# Connectors.net
KiCad netlist of a schematic drawn in Altium Designer
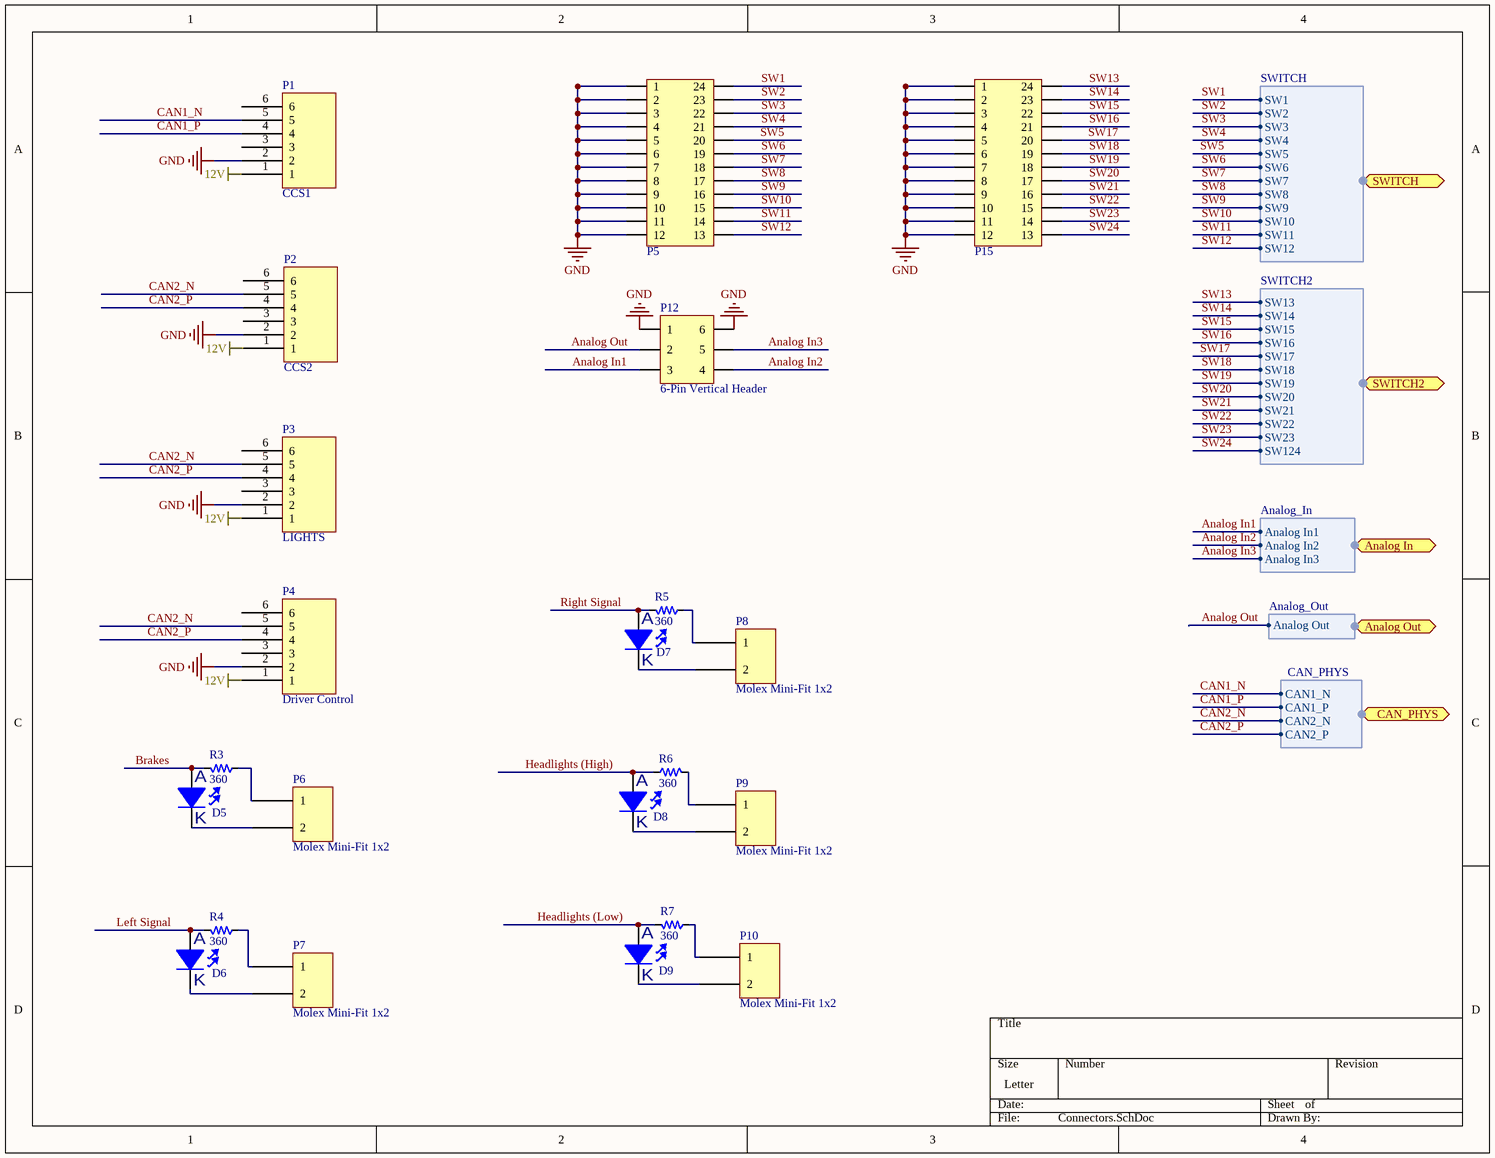
[diagram p0: Connectors.SchDoc]

(export (version "E")
  (design (tool "Eeschema 10.0.6"))
  (components
    (comp (ref "D5")
      (value "LED RED")
      (footprint "RED LED")
      (libsource (lib "LED RED 150141RS73100") (part "LED RED"))
    )
    (comp (ref "D6")
      (value "LED RED")
      (footprint "RED LED")
      (libsource (lib "LED RED 150141RS73100") (part "LED RED"))
    )
    (comp (ref "D7")
      (value "LED RED")
      (footprint "RED LED")
      (libsource (lib "LED RED 150141RS73100") (part "LED RED"))
    )
    (comp (ref "D8")
      (value "LED RED")
      (footprint "RED LED")
      (libsource (lib "LED RED 150141RS73100") (part "LED RED"))
    )
    (comp (ref "D9")
      (value "LED RED")
      (footprint "RED LED")
      (libsource (lib "LED RED 150141RS73100") (part "LED RED"))
    )
    (comp (ref "P1")
      (value "CCS1")
      (footprint "PCB_MLX_MICROFIT_3X2")
      (libsource (lib "SCH_MLX_MICROFIT_3X2_P") (part "SCH_MLX_MICROFIT_3X2"))
    )
    (comp (ref "P2")
      (value "CCS2")
      (footprint "PCB_MLX_MICROFIT_3X2")
      (libsource (lib "SCH_MLX_MICROFIT_3X2_P") (part "SCH_MLX_MICROFIT_3X2"))
    )
    (comp (ref "P3")
      (value "LIGHTS")
      (footprint "PCB_MLX_MICROFIT_3X2")
      (libsource (lib "SCH_MLX_MICROFIT_3X2_P") (part "SCH_MLX_MICROFIT_3X2"))
    )
    (comp (ref "P4")
      (value "Driver Control")
      (footprint "PCB_MLX_MICROFIT_3X2")
      (libsource (lib "SCH_MLX_MICROFIT_3X2_P") (part "SCH_MLX_MICROFIT_3X2"))
    )
    (comp (ref "P5")
      (value "24-Pin Vertical Header")
      (footprint "24-Pin Vertical Header")
      (fields (field (name "MANUFACTURER") "Sullins"))
      (libsource (lib "24 Pin 100 mil Vertical Header - Through Hole") (part "24-Pin Vertical Header"))
    )
    (comp (ref "P6")
      (value "Molex Mini-Fit 1x2")
      (footprint "Molex Mini-Fit Jr 2x1")
      (libsource (lib "Molex Mini-Fit Jr 1x2") (part "Molex Mini-Fit 1x2"))
    )
    (comp (ref "P7")
      (value "Molex Mini-Fit 1x2")
      (footprint "Molex Mini-Fit Jr 2x1")
      (libsource (lib "Molex Mini-Fit Jr 1x2") (part "Molex Mini-Fit 1x2"))
    )
    (comp (ref "P8")
      (value "Molex Mini-Fit 1x2")
      (footprint "Molex Mini-Fit Jr 2x1")
      (libsource (lib "Molex Mini-Fit Jr 1x2") (part "Molex Mini-Fit 1x2"))
    )
    (comp (ref "P9")
      (value "Molex Mini-Fit 1x2")
      (footprint "Molex Mini-Fit Jr 2x1")
      (libsource (lib "Molex Mini-Fit Jr 1x2") (part "Molex Mini-Fit 1x2"))
    )
    (comp (ref "P10")
      (value "Molex Mini-Fit 1x2")
      (footprint "Molex Mini-Fit Jr 2x1")
      (libsource (lib "Molex Mini-Fit Jr 1x2") (part "Molex Mini-Fit 1x2"))
    )
    (comp (ref "P12")
      (value "6-Pin Vertical Header")
      (footprint "6-Pin Vertical Header")
      (fields (field (name "MANUFACTURER") "Sullins"))
      (libsource (lib "6 Pin 100 mil Vertical Header - Through Hole") (part "6-Pin Vertical Header"))
    )
    (comp (ref "P15")
      (value "24-Pin Vertical Header")
      (footprint "24-Pin Vertical Header")
      (fields (field (name "MANUFACTURER") "Sullins"))
      (libsource (lib "24 Pin 100 mil Vertical Header - Through Hole") (part "24-Pin Vertical Header"))
    )
    (comp (ref "R3")
      (value "SCH_GENERIC_RESISTOR_0603")
      (footprint "PCB_GENERIC_SMD_0603")
      (description "Generic SMD resistor 0603")
      (fields (field (name "RESISTANCE") "360"))
      (libsource (lib "SCH_GENERIC_RESISTOR_0603") (part "SCH_GENERIC_RESISTOR_0603"))
    )
    (comp (ref "R4")
      (value "SCH_GENERIC_RESISTOR_0603")
      (footprint "PCB_GENERIC_SMD_0603")
      (description "Generic SMD resistor 0603")
      (fields (field (name "RESISTANCE") "360"))
      (libsource (lib "SCH_GENERIC_RESISTOR_0603") (part "SCH_GENERIC_RESISTOR_0603"))
    )
    (comp (ref "R5")
      (value "SCH_GENERIC_RESISTOR_0603")
      (footprint "PCB_GENERIC_SMD_0603")
      (description "Generic SMD resistor 0603")
      (fields (field (name "RESISTANCE") "360"))
      (libsource (lib "SCH_GENERIC_RESISTOR_0603") (part "SCH_GENERIC_RESISTOR_0603"))
    )
    (comp (ref "R6")
      (value "SCH_GENERIC_RESISTOR_0603")
      (footprint "PCB_GENERIC_SMD_0603")
      (description "Generic SMD resistor 0603")
      (fields (field (name "RESISTANCE") "360"))
      (libsource (lib "SCH_GENERIC_RESISTOR_0603") (part "SCH_GENERIC_RESISTOR_0603"))
    )
    (comp (ref "R7")
      (value "SCH_GENERIC_RESISTOR_0603")
      (footprint "PCB_GENERIC_SMD_0603")
      (description "Generic SMD resistor 0603")
      (fields (field (name "RESISTANCE") "360"))
      (libsource (lib "SCH_GENERIC_RESISTOR_0603") (part "SCH_GENERIC_RESISTOR_0603"))
    )
  )
  (nets
    (net (code "6") (name "/Analog In1") (class "Default")
      (node (ref "P12") (pin "3") (pinfunction "3_3") (pintype "passive"))
    )
    (net (code "7") (name "/Analog In2") (class "Default")
      (node (ref "P12") (pin "4") (pinfunction "4_4") (pintype "passive"))
    )
    (net (code "8") (name "/Analog In3") (class "Default")
      (node (ref "P12") (pin "5") (pinfunction "5_5") (pintype "passive"))
    )
    (net (code "9") (name "/Analog Out") (class "Default")
      (node (ref "P12") (pin "2") (pinfunction "2_2") (pintype "passive"))
    )
    (net (code "10") (name "/Brakes") (class "Default")
      (node (ref "D5") (pin "2") (pintype "passive"))
      (node (ref "R3") (pin "2") (pinfunction "2_2") (pintype "passive"))
    )
    (net (code "11") (name "/CAN1_N") (class "Default")
      (node (ref "P1") (pin "5") (pinfunction "5_5") (pintype "passive"))
    )
    (net (code "12") (name "/CAN1_P") (class "Default")
      (node (ref "P1") (pin "4") (pinfunction "4_4") (pintype "passive"))
    )
    (net (code "13") (name "/CAN2_N") (class "Default")
      (node (ref "P2") (pin "5") (pinfunction "5_5") (pintype "passive"))
      (node (ref "P3") (pin "5") (pinfunction "5_5") (pintype "passive"))
      (node (ref "P4") (pin "5") (pinfunction "5_5") (pintype "passive"))
    )
    (net (code "14") (name "/CAN2_P") (class "Default")
      (node (ref "P2") (pin "4") (pinfunction "4_4") (pintype "passive"))
      (node (ref "P3") (pin "4") (pinfunction "4_4") (pintype "passive"))
      (node (ref "P4") (pin "4") (pinfunction "4_4") (pintype "passive"))
    )
    (net (code "15") (name "/Headlights (High)") (class "Default")
      (node (ref "D8") (pin "2") (pintype "passive"))
      (node (ref "R6") (pin "1") (pinfunction "1_1") (pintype "passive"))
    )
    (net (code "16") (name "/Headlights (Low)") (class "Default")
      (node (ref "D9") (pin "2") (pintype "passive"))
      (node (ref "R7") (pin "2") (pinfunction "2_2") (pintype "passive"))
    )
    (net (code "17") (name "/Left Signal") (class "Default")
      (node (ref "D6") (pin "2") (pintype "passive"))
      (node (ref "R4") (pin "2") (pinfunction "2_2") (pintype "passive"))
    )
    (net (code "18") (name "/Right Signal") (class "Default")
      (node (ref "D7") (pin "2") (pintype "passive"))
      (node (ref "R5") (pin "2") (pinfunction "2_2") (pintype "passive"))
    )
    (net (code "19") (name "/SW1") (class "Default")
      (node (ref "P5") (pin "24") (pinfunction "24_24") (pintype "passive"))
    )
    (net (code "20") (name "/SW2") (class "Default")
      (node (ref "P5") (pin "23") (pinfunction "23_23") (pintype "passive"))
    )
    (net (code "21") (name "/SW3") (class "Default")
      (node (ref "P5") (pin "22") (pinfunction "22_22") (pintype "passive"))
    )
    (net (code "22") (name "/SW4") (class "Default")
      (node (ref "P5") (pin "21") (pinfunction "21_21") (pintype "passive"))
    )
    (net (code "23") (name "/SW5") (class "Default")
      (node (ref "P5") (pin "20") (pinfunction "20_20") (pintype "passive"))
    )
    (net (code "24") (name "/SW6") (class "Default")
      (node (ref "P5") (pin "19") (pinfunction "19_19") (pintype "passive"))
    )
    (net (code "25") (name "/SW7") (class "Default")
      (node (ref "P5") (pin "18") (pinfunction "18_18") (pintype "passive"))
    )
    (net (code "26") (name "/SW8") (class "Default")
      (node (ref "P5") (pin "17") (pinfunction "17_17") (pintype "passive"))
    )
    (net (code "27") (name "/SW9") (class "Default")
      (node (ref "P5") (pin "16") (pinfunction "16_16") (pintype "passive"))
    )
    (net (code "28") (name "/SW10") (class "Default")
      (node (ref "P5") (pin "15") (pinfunction "15_15") (pintype "passive"))
    )
    (net (code "29") (name "/SW11") (class "Default")
      (node (ref "P5") (pin "14") (pinfunction "14_14") (pintype "passive"))
    )
    (net (code "30") (name "/SW12") (class "Default")
      (node (ref "P5") (pin "13") (pinfunction "13_13") (pintype "passive"))
    )
    (net (code "31") (name "/SW13") (class "Default")
      (node (ref "P15") (pin "24") (pinfunction "24_24") (pintype "passive"))
    )
    (net (code "32") (name "/SW14") (class "Default")
      (node (ref "P15") (pin "23") (pinfunction "23_23") (pintype "passive"))
    )
    (net (code "33") (name "/SW15") (class "Default")
      (node (ref "P15") (pin "22") (pinfunction "22_22") (pintype "passive"))
    )
    (net (code "34") (name "/SW16") (class "Default")
      (node (ref "P15") (pin "21") (pinfunction "21_21") (pintype "passive"))
    )
    (net (code "35") (name "/SW17") (class "Default")
      (node (ref "P15") (pin "20") (pinfunction "20_20") (pintype "passive"))
    )
    (net (code "36") (name "/SW18") (class "Default")
      (node (ref "P15") (pin "19") (pinfunction "19_19") (pintype "passive"))
    )
    (net (code "37") (name "/SW19") (class "Default")
      (node (ref "P15") (pin "18") (pinfunction "18_18") (pintype "passive"))
    )
    (net (code "38") (name "/SW20") (class "Default")
      (node (ref "P15") (pin "17") (pinfunction "17_17") (pintype "passive"))
    )
    (net (code "39") (name "/SW21") (class "Default")
      (node (ref "P15") (pin "16") (pinfunction "16_16") (pintype "passive"))
    )
    (net (code "40") (name "/SW22") (class "Default")
      (node (ref "P15") (pin "15") (pinfunction "15_15") (pintype "passive"))
    )
    (net (code "41") (name "/SW23") (class "Default")
      (node (ref "P15") (pin "14") (pinfunction "14_14") (pintype "passive"))
    )
    (net (code "42") (name "/SW24") (class "Default")
      (node (ref "P15") (pin "13") (pinfunction "13_13") (pintype "passive"))
    )
    (net (code "48") (name "12V") (class "Default")
      (node (ref "P1") (pin "1") (pinfunction "1_1") (pintype "passive"))
      (node (ref "P2") (pin "1") (pinfunction "1_1") (pintype "passive"))
      (node (ref "P3") (pin "1") (pinfunction "1_1") (pintype "passive"))
      (node (ref "P4") (pin "1") (pinfunction "1_1") (pintype "passive"))
    )
    (net (code "49") (name "GND") (class "Default")
      (node (ref "P1") (pin "2") (pinfunction "2_2") (pintype "passive"))
      (node (ref "P12") (pin "1") (pinfunction "1_1") (pintype "passive"))
      (node (ref "P12") (pin "6") (pinfunction "6_6") (pintype "passive"))
      (node (ref "P15") (pin "1") (pinfunction "1_1") (pintype "passive"))
      (node (ref "P15") (pin "10") (pinfunction "10_10") (pintype "passive"))
      (node (ref "P15") (pin "11") (pinfunction "11_11") (pintype "passive"))
      (node (ref "P15") (pin "12") (pinfunction "12_12") (pintype "passive"))
      (node (ref "P15") (pin "2") (pinfunction "2_2") (pintype "passive"))
      (node (ref "P15") (pin "3") (pinfunction "3_3") (pintype "passive"))
      (node (ref "P15") (pin "4") (pinfunction "4_4") (pintype "passive"))
      (node (ref "P15") (pin "5") (pinfunction "5_5") (pintype "passive"))
      (node (ref "P15") (pin "6") (pinfunction "6_6") (pintype "passive"))
      (node (ref "P15") (pin "7") (pinfunction "7_7") (pintype "passive"))
      (node (ref "P15") (pin "8") (pinfunction "8_8") (pintype "passive"))
      (node (ref "P15") (pin "9") (pinfunction "9_9") (pintype "passive"))
      (node (ref "P2") (pin "2") (pinfunction "2_2") (pintype "passive"))
      (node (ref "P3") (pin "2") (pinfunction "2_2") (pintype "passive"))
      (node (ref "P4") (pin "2") (pinfunction "2_2") (pintype "passive"))
      (node (ref "P5") (pin "1") (pinfunction "1_1") (pintype "passive"))
      (node (ref "P5") (pin "10") (pinfunction "10_10") (pintype "passive"))
      (node (ref "P5") (pin "11") (pinfunction "11_11") (pintype "passive"))
      (node (ref "P5") (pin "12") (pinfunction "12_12") (pintype "passive"))
      (node (ref "P5") (pin "2") (pinfunction "2_2") (pintype "passive"))
      (node (ref "P5") (pin "3") (pinfunction "3_3") (pintype "passive"))
      (node (ref "P5") (pin "4") (pinfunction "4_4") (pintype "passive"))
      (node (ref "P5") (pin "5") (pinfunction "5_5") (pintype "passive"))
      (node (ref "P5") (pin "6") (pinfunction "6_6") (pintype "passive"))
      (node (ref "P5") (pin "7") (pinfunction "7_7") (pintype "passive"))
      (node (ref "P5") (pin "8") (pinfunction "8_8") (pintype "passive"))
      (node (ref "P5") (pin "9") (pinfunction "9_9") (pintype "passive"))
    )
    (net (code "50") (name "Net-(D5-Pad1)") (class "Default")
      (node (ref "D5") (pin "1") (pintype "passive"))
      (node (ref "P6") (pin "2") (pinfunction "2_2") (pintype "passive"))
    )
    (net (code "51") (name "Net-(D6-Pad1)") (class "Default")
      (node (ref "D6") (pin "1") (pintype "passive"))
      (node (ref "P7") (pin "2") (pinfunction "2_2") (pintype "passive"))
    )
    (net (code "52") (name "Net-(D7-Pad1)") (class "Default")
      (node (ref "D7") (pin "1") (pintype "passive"))
      (node (ref "P8") (pin "2") (pinfunction "2_2") (pintype "passive"))
    )
    (net (code "53") (name "Net-(D8-Pad1)") (class "Default")
      (node (ref "D8") (pin "1") (pintype "passive"))
      (node (ref "P9") (pin "2") (pinfunction "2_2") (pintype "passive"))
    )
    (net (code "54") (name "Net-(D9-Pad1)") (class "Default")
      (node (ref "D9") (pin "1") (pintype "passive"))
      (node (ref "P10") (pin "2") (pinfunction "2_2") (pintype "passive"))
    )
    (net (code "55") (name "Net-(P6-Pad1)") (class "Default")
      (node (ref "P6") (pin "1") (pinfunction "1_1") (pintype "passive"))
      (node (ref "R3") (pin "1") (pinfunction "1_1") (pintype "passive"))
    )
    (net (code "56") (name "Net-(P7-Pad1)") (class "Default")
      (node (ref "P7") (pin "1") (pinfunction "1_1") (pintype "passive"))
      (node (ref "R4") (pin "1") (pinfunction "1_1") (pintype "passive"))
    )
    (net (code "57") (name "Net-(P8-Pad1)") (class "Default")
      (node (ref "P8") (pin "1") (pinfunction "1_1") (pintype "passive"))
      (node (ref "R5") (pin "1") (pinfunction "1_1") (pintype "passive"))
    )
    (net (code "58") (name "Net-(P9-Pad1)") (class "Default")
      (node (ref "P9") (pin "1") (pinfunction "1_1") (pintype "passive"))
      (node (ref "R6") (pin "2") (pinfunction "2_2") (pintype "passive"))
    )
    (net (code "59") (name "Net-(P10-Pad1)") (class "Default")
      (node (ref "P10") (pin "1") (pinfunction "1_1") (pintype "passive"))
      (node (ref "R7") (pin "1") (pinfunction "1_1") (pintype "passive"))
    )
    (net (code "60") (name "unconnected-(P1-Pad3)") (class "Default")
      (node (ref "P1") (pin "3") (pinfunction "3_3") (pintype "passive"))
    )
    (net (code "61") (name "unconnected-(P1-Pad6)") (class "Default")
      (node (ref "P1") (pin "6") (pinfunction "6_6") (pintype "passive"))
    )
    (net (code "62") (name "unconnected-(P2-Pad3)") (class "Default")
      (node (ref "P2") (pin "3") (pinfunction "3_3") (pintype "passive"))
    )
    (net (code "63") (name "unconnected-(P2-Pad6)") (class "Default")
      (node (ref "P2") (pin "6") (pinfunction "6_6") (pintype "passive"))
    )
    (net (code "64") (name "unconnected-(P3-Pad3)") (class "Default")
      (node (ref "P3") (pin "3") (pinfunction "3_3") (pintype "passive"))
    )
    (net (code "65") (name "unconnected-(P3-Pad6)") (class "Default")
      (node (ref "P3") (pin "6") (pinfunction "6_6") (pintype "passive"))
    )
    (net (code "66") (name "unconnected-(P4-Pad3)") (class "Default")
      (node (ref "P4") (pin "3") (pinfunction "3_3") (pintype "passive"))
    )
    (net (code "67") (name "unconnected-(P4-Pad6)") (class "Default")
      (node (ref "P4") (pin "6") (pinfunction "6_6") (pintype "passive"))
    )
  )
)
